# VM_Motor_v0t8.net
KiCad netlist of a schematic drawn in EAGLE
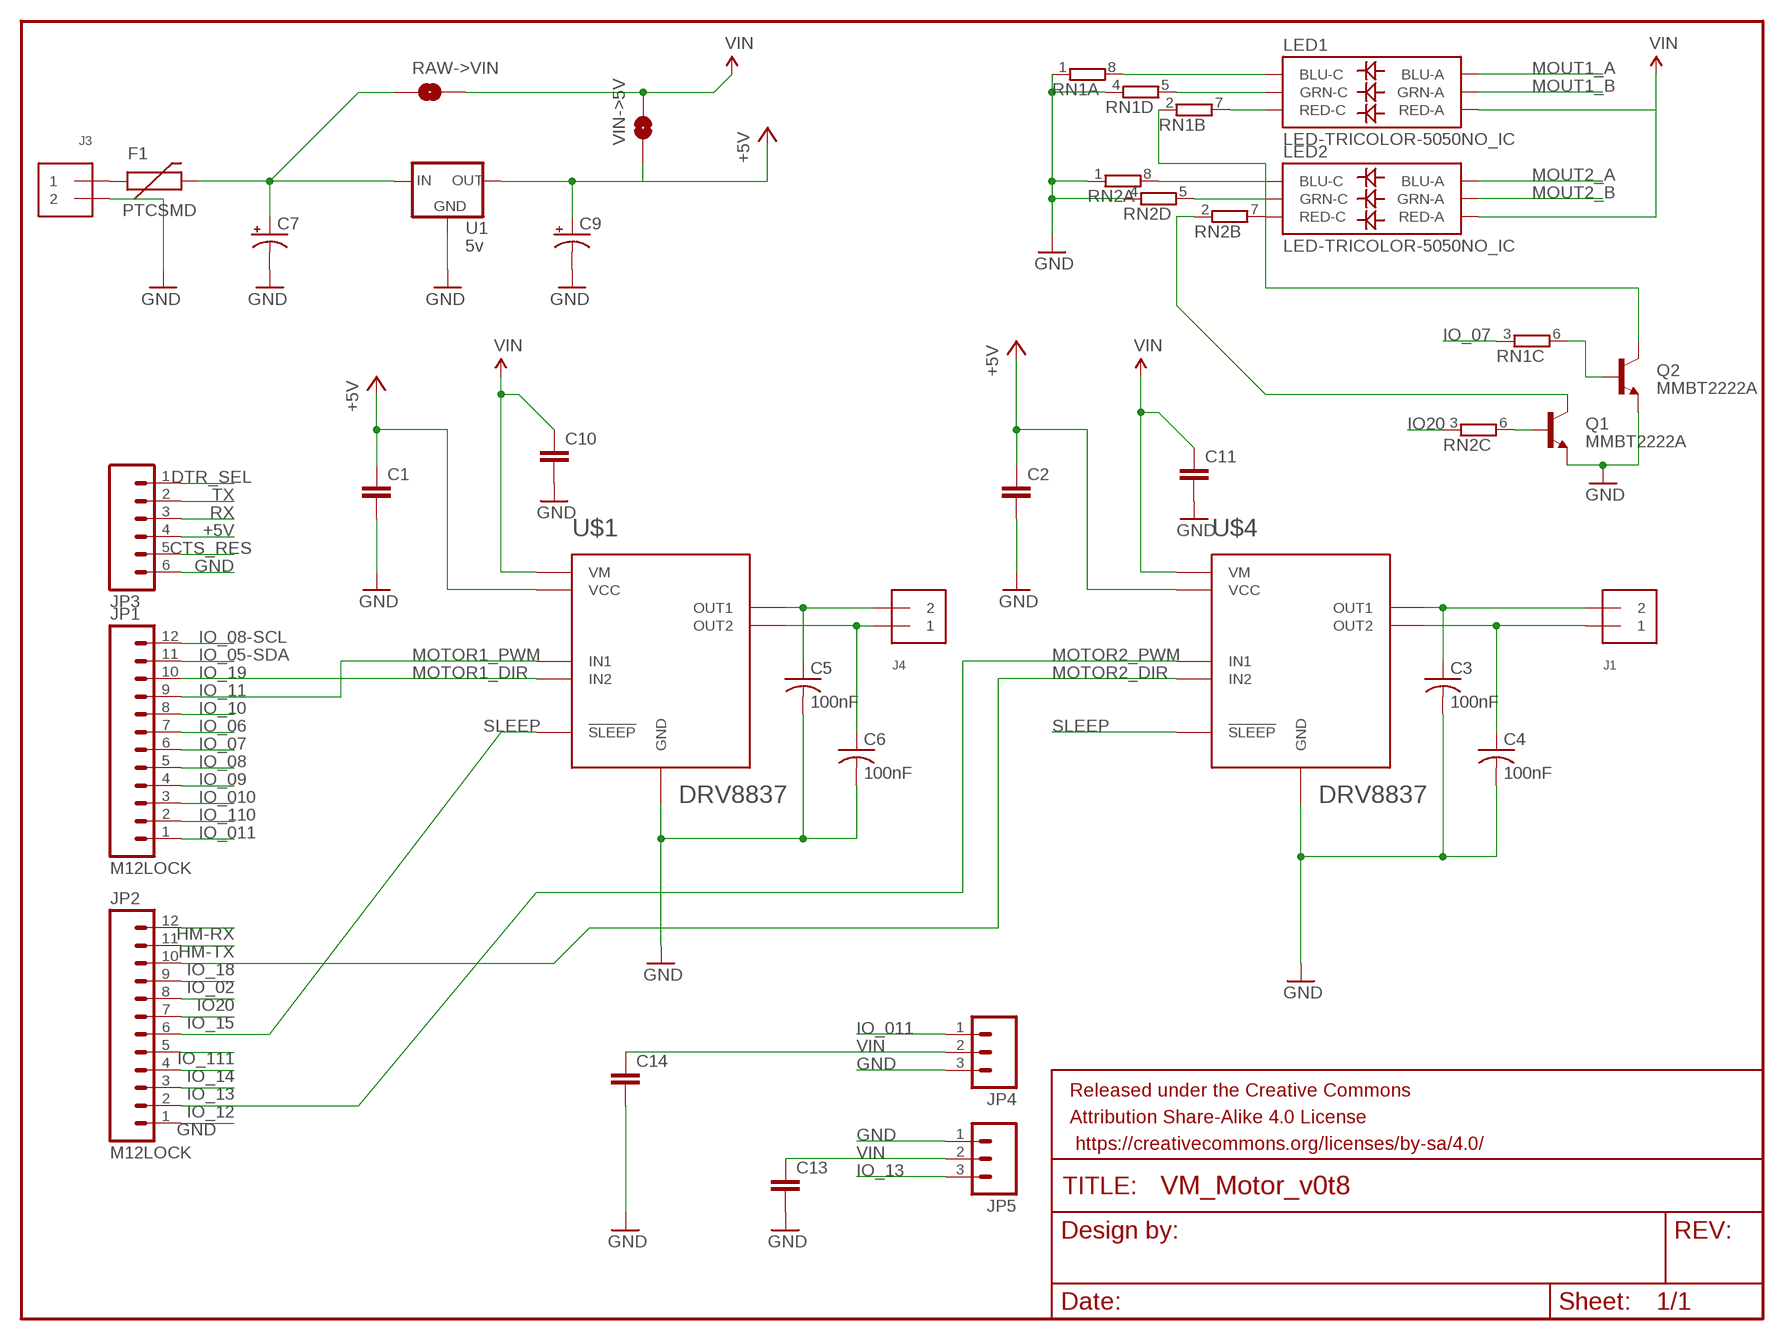
[diagram p0: schematic, sheet 1]

(export (version "E")
  (design (tool "Eeschema 10.0.6"))
  (components
    (comp (ref "C1")
      (value "CAP0402-CAP")
      (footprint "eagle-import:0402-CAP")
      (libsource (lib "eagle-import") (part "CAP0402-CAP"))
    )
    (comp (ref "C2")
      (value "CAP0402-CAP")
      (footprint "eagle-import:0402-CAP")
      (libsource (lib "eagle-import") (part "CAP0402-CAP"))
    )
    (comp (ref "C3")
      (value "100nF")
      (footprint "eagle-import:C0402")
      (libsource (lib "eagle-import") (part "C-USC0402"))
    )
    (comp (ref "C4")
      (value "100nF")
      (footprint "eagle-import:C0402")
      (libsource (lib "eagle-import") (part "C-USC0402"))
    )
    (comp (ref "C5")
      (value "100nF")
      (footprint "eagle-import:C0402")
      (libsource (lib "eagle-import") (part "C-USC0402"))
    )
    (comp (ref "C6")
      (value "100nF")
      (footprint "eagle-import:C0402")
      (libsource (lib "eagle-import") (part "C-USC0402"))
    )
    (comp (ref "C7")
      (value "CPOL-US150CLZ-0810")
      (footprint "eagle-import:150CLZ-0810")
      (libsource (lib "eagle-import") (part "CPOL-US150CLZ-0810"))
    )
    (comp (ref "C9")
      (value "CPOL-US150CLZ-0810")
      (footprint "eagle-import:150CLZ-0810")
      (libsource (lib "eagle-import") (part "CPOL-US150CLZ-0810"))
    )
    (comp (ref "C10")
      (value "CAP0402-CAP")
      (footprint "eagle-import:0402-CAP")
      (libsource (lib "eagle-import") (part "CAP0402-CAP"))
    )
    (comp (ref "C11")
      (value "CAP0402-CAP")
      (footprint "eagle-import:0402-CAP")
      (libsource (lib "eagle-import") (part "CAP0402-CAP"))
    )
    (comp (ref "C13")
      (value "CAP0402-CAP")
      (footprint "eagle-import:0402-CAP")
      (libsource (lib "eagle-import") (part "CAP0402-CAP"))
    )
    (comp (ref "C14")
      (value "CAP0402-CAP")
      (footprint "eagle-import:0402-CAP")
      (libsource (lib "eagle-import") (part "CAP0402-CAP"))
    )
    (comp (ref "F1")
      (value "PTCSMD")
      (footprint "eagle-import:PTC-1206")
      (libsource (lib "eagle-import") (part "PTCSMD"))
    )
    (comp (ref "FRAME1")
      (value "FRAME-LETTER")
      (footprint "eagle-import:CREATIVE_COMMONS")
      (libsource (lib "eagle-import") (part "FRAME-LETTER"))
    )
    (comp (ref "J1")
      (value "TERMBLOCK_1X2")
      (footprint "eagle-import:TERMBLOCK_1X2-3.5MM")
      (libsource (lib "eagle-import") (part "TERMBLOCK_1X2"))
    )
    (comp (ref "J3")
      (value "TERMBLOCK_1X2")
      (footprint "eagle-import:TERMBLOCK_1X2-3.5MM")
      (libsource (lib "eagle-import") (part "TERMBLOCK_1X2"))
    )
    (comp (ref "J4")
      (value "TERMBLOCK_1X2")
      (footprint "eagle-import:TERMBLOCK_1X2-3.5MM")
      (libsource (lib "eagle-import") (part "TERMBLOCK_1X2"))
    )
    (comp (ref "JP1")
      (value "M12LOCK")
      (footprint "eagle-import:1X12_LOCK")
      (libsource (lib "eagle-import") (part "M12LOCK"))
    )
    (comp (ref "JP2")
      (value "M12LOCK")
      (footprint "eagle-import:1X12_LOCK")
      (libsource (lib "eagle-import") (part "M12LOCK"))
    )
    (comp (ref "JP3")
      (value "M06LOCK")
      (footprint "eagle-import:1X06_LOCK")
      (libsource (lib "eagle-import") (part "M06LOCK"))
    )
    (comp (ref "JP4")
      (value "M03LOCK")
      (footprint "eagle-import:1X03_LOCK")
      (libsource (lib "eagle-import") (part "M03LOCK"))
    )
    (comp (ref "JP5")
      (value "M03LOCK")
      (footprint "eagle-import:1X03_LOCK")
      (libsource (lib "eagle-import") (part "M03LOCK"))
    )
    (comp (ref "LED1")
      (value "LED-TRICOLOR-5050NO_IC")
      (footprint "eagle-import:LED-TRICOLOR-5050")
      (libsource (lib "eagle-import") (part "LED-TRICOLOR-5050NO_IC"))
    )
    (comp (ref "LED2")
      (value "LED-TRICOLOR-5050NO_IC")
      (footprint "eagle-import:LED-TRICOLOR-5050")
      (libsource (lib "eagle-import") (part "LED-TRICOLOR-5050NO_IC"))
    )
    (comp (ref "Q1")
      (value "MMBT2222A")
      (footprint "eagle-import:SOT23-3")
      (libsource (lib "eagle-import") (part "TRANSISTOR_NPNMMBT2222A"))
    )
    (comp (ref "Q2")
      (value "MMBT2222A")
      (footprint "eagle-import:SOT23-3")
      (libsource (lib "eagle-import") (part "TRANSISTOR_NPNMMBT2222A"))
    )
    (comp (ref "RAW->VIN")
      (value "SOLDERJUMPERNO")
      (footprint "eagle-import:SJ_2S-NO")
      (libsource (lib "eagle-import") (part "SOLDERJUMPERNO"))
    )
    (comp (ref "RN1")
      (value "4R-N0402ARV341")
      (footprint "eagle-import:4X0402ARV341")
      (libsource (lib "eagle-import") (part "4R-N0402ARV341"))
    )
    (comp (ref "RN2")
      (value "4R-N0402ARV341")
      (footprint "eagle-import:4X0402ARV341")
      (libsource (lib "eagle-import") (part "4R-N0402ARV341"))
    )
    (comp (ref "U$1")
      (value "DRV8837")
      (footprint "eagle-import:QFN8")
      (libsource (lib "eagle-import") (part "DRV8837"))
    )
    (comp (ref "U$4")
      (value "DRV8837")
      (footprint "eagle-import:QFN8")
      (libsource (lib "eagle-import") (part "DRV8837"))
    )
    (comp (ref "U1")
      (value "5v")
      (footprint "eagle-import:DPAK")
      (libsource (lib "eagle-import") (part "V_REG_MC33269DT"))
    )
    (comp (ref "VIN->5V")
      (value "SOLDERJUMPERNO")
      (footprint "eagle-import:SJ_2S-NO")
      (libsource (lib "eagle-import") (part "SOLDERJUMPERNO"))
    )
  )
  (nets
    (net (code "1") (name "+5V") (class "Default")
      (node (ref "C1") (pin "1") (pinfunction "1_1") (pintype "passive"))
      (node (ref "C2") (pin "1") (pinfunction "1_1") (pintype "passive"))
      (node (ref "C9") (pin "+") (pinfunction "+_+") (pintype "passive"))
      (node (ref "JP3") (pin "4") (pinfunction "4_4") (pintype "passive"))
      (node (ref "U$1") (pin "P$8") (pinfunction "VCC_P$8") (pintype "bidirectional"))
      (node (ref "U$4") (pin "P$8") (pinfunction "VCC_P$8") (pintype "bidirectional"))
      (node (ref "U1") (pin "4") (pinfunction "OUT_4") (pintype "output"))
      (node (ref "VIN->5V") (pin "1") (pinfunction "1_1") (pintype "passive"))
    )
    (net (code "2") (name "/CTS_RES") (class "Default")
      (node (ref "JP3") (pin "5") (pinfunction "5_5") (pintype "passive"))
    )
    (net (code "3") (name "/DTR_SEL") (class "Default")
      (node (ref "JP3") (pin "1") (pinfunction "1_1") (pintype "passive"))
    )
    (net (code "4") (name "/HM-RX") (class "Default")
      (node (ref "JP2") (pin "12") (pinfunction "12_12") (pintype "passive"))
    )
    (net (code "5") (name "/HM-TX") (class "Default")
      (node (ref "JP2") (pin "11") (pinfunction "11_11") (pintype "passive"))
    )
    (net (code "6") (name "/IO20") (class "Default")
      (node (ref "JP2") (pin "8") (pinfunction "8_8") (pintype "passive"))
      (node (ref "RN2") (pin "3") (pinfunction "1_3") (pintype "passive"))
    )
    (net (code "7") (name "/IO_02") (class "Default")
      (node (ref "JP2") (pin "9") (pinfunction "9_9") (pintype "passive"))
    )
    (net (code "8") (name "/IO_05-SDA") (class "Default")
      (node (ref "JP1") (pin "11") (pinfunction "11_11") (pintype "passive"))
    )
    (net (code "9") (name "/IO_06") (class "Default")
      (node (ref "JP1") (pin "7") (pinfunction "7_7") (pintype "passive"))
    )
    (net (code "10") (name "/IO_07") (class "Default")
      (node (ref "JP1") (pin "6") (pinfunction "6_6") (pintype "passive"))
      (node (ref "RN1") (pin "3") (pinfunction "1_3") (pintype "passive"))
    )
    (net (code "11") (name "/IO_08") (class "Default")
      (node (ref "JP1") (pin "5") (pinfunction "5_5") (pintype "passive"))
    )
    (net (code "12") (name "/IO_08-SCL") (class "Default")
      (node (ref "JP1") (pin "12") (pinfunction "12_12") (pintype "passive"))
    )
    (net (code "13") (name "/IO_09") (class "Default")
      (node (ref "JP1") (pin "4") (pinfunction "4_4") (pintype "passive"))
    )
    (net (code "14") (name "/IO_10") (class "Default")
      (node (ref "JP1") (pin "8") (pinfunction "8_8") (pintype "passive"))
    )
    (net (code "15") (name "/IO_010") (class "Default")
      (node (ref "JP1") (pin "3") (pinfunction "3_3") (pintype "passive"))
    )
    (net (code "16") (name "/IO_011") (class "Default")
      (node (ref "JP1") (pin "1") (pinfunction "1_1") (pintype "passive"))
      (node (ref "JP4") (pin "1") (pinfunction "1_1") (pintype "passive"))
    )
    (net (code "17") (name "/IO_13") (class "Default")
      (node (ref "JP2") (pin "3") (pinfunction "3_3") (pintype "passive"))
      (node (ref "JP5") (pin "3") (pinfunction "3_3") (pintype "passive"))
    )
    (net (code "18") (name "/IO_14") (class "Default")
      (node (ref "JP2") (pin "4") (pinfunction "4_4") (pintype "passive"))
    )
    (net (code "19") (name "/IO_15") (class "Default")
      (node (ref "JP2") (pin "7") (pinfunction "7_7") (pintype "passive"))
    )
    (net (code "20") (name "/IO_110") (class "Default")
      (node (ref "JP1") (pin "2") (pinfunction "2_2") (pintype "passive"))
    )
    (net (code "21") (name "/IO_111") (class "Default")
      (node (ref "JP2") (pin "5") (pinfunction "5_5") (pintype "passive"))
    )
    (net (code "22") (name "/MOTOR1_DIR") (class "Default")
      (node (ref "JP1") (pin "10") (pinfunction "10_10") (pintype "passive"))
      (node (ref "U$1") (pin "P$5") (pinfunction "IN2_P$5") (pintype "bidirectional"))
    )
    (net (code "23") (name "/MOTOR1_PWM") (class "Default")
      (node (ref "JP1") (pin "9") (pinfunction "9_9") (pintype "passive"))
      (node (ref "U$1") (pin "P$6") (pinfunction "IN1_P$6") (pintype "bidirectional"))
    )
    (net (code "24") (name "/MOTOR2_DIR") (class "Default")
      (node (ref "JP2") (pin "10") (pinfunction "10_10") (pintype "passive"))
      (node (ref "U$4") (pin "P$5") (pinfunction "IN2_P$5") (pintype "bidirectional"))
    )
    (net (code "25") (name "/MOTOR2_PWM") (class "Default")
      (node (ref "JP2") (pin "2") (pinfunction "2_2") (pintype "passive"))
      (node (ref "U$4") (pin "P$6") (pinfunction "IN1_P$6") (pintype "bidirectional"))
    )
    (net (code "26") (name "/MOUT1_A") (class "Default")
      (node (ref "C5") (pin "1") (pinfunction "1_1") (pintype "passive"))
      (node (ref "J4") (pin "2") (pinfunction "2_2") (pintype "passive"))
      (node (ref "LED1") (pin "3") (pinfunction "BLU-A_3") (pintype "bidirectional"))
      (node (ref "U$1") (pin "P$2") (pinfunction "OUT1_P$2") (pintype "bidirectional"))
    )
    (net (code "27") (name "/MOUT1_B") (class "Default")
      (node (ref "C6") (pin "1") (pinfunction "1_1") (pintype "passive"))
      (node (ref "J4") (pin "1") (pinfunction "1_1") (pintype "passive"))
      (node (ref "LED1") (pin "1") (pinfunction "GRN-A_1") (pintype "bidirectional"))
      (node (ref "U$1") (pin "P$3") (pinfunction "OUT2_P$3") (pintype "bidirectional"))
    )
    (net (code "28") (name "/MOUT2_A") (class "Default")
      (node (ref "C3") (pin "1") (pinfunction "1_1") (pintype "passive"))
      (node (ref "J1") (pin "2") (pinfunction "2_2") (pintype "passive"))
      (node (ref "LED2") (pin "3") (pinfunction "BLU-A_3") (pintype "bidirectional"))
      (node (ref "U$4") (pin "P$2") (pinfunction "OUT1_P$2") (pintype "bidirectional"))
    )
    (net (code "29") (name "/MOUT2_B") (class "Default")
      (node (ref "C4") (pin "1") (pinfunction "1_1") (pintype "passive"))
      (node (ref "J1") (pin "1") (pinfunction "1_1") (pintype "passive"))
      (node (ref "LED2") (pin "1") (pinfunction "GRN-A_1") (pintype "bidirectional"))
      (node (ref "U$4") (pin "P$3") (pinfunction "OUT2_P$3") (pintype "bidirectional"))
    )
    (net (code "30") (name "/RX") (class "Default")
      (node (ref "JP3") (pin "3") (pinfunction "3_3") (pintype "passive"))
    )
    (net (code "31") (name "/SLEEP") (class "Default")
      (node (ref "JP2") (pin "6") (pinfunction "6_6") (pintype "passive"))
      (node (ref "U$1") (pin "P$7") (pinfunction "~{SLEEP}_P$7") (pintype "bidirectional"))
      (node (ref "U$4") (pin "P$7") (pinfunction "~{SLEEP}_P$7") (pintype "bidirectional"))
    )
    (net (code "32") (name "/TX") (class "Default")
      (node (ref "JP3") (pin "2") (pinfunction "2_2") (pintype "passive"))
    )
    (net (code "33") (name "GND") (class "Default")
      (node (ref "C1") (pin "2") (pinfunction "2_2") (pintype "passive"))
      (node (ref "C10") (pin "2") (pinfunction "2_2") (pintype "passive"))
      (node (ref "C11") (pin "2") (pinfunction "2_2") (pintype "passive"))
      (node (ref "C13") (pin "2") (pinfunction "2_2") (pintype "passive"))
      (node (ref "C14") (pin "2") (pinfunction "2_2") (pintype "passive"))
      (node (ref "C2") (pin "2") (pinfunction "2_2") (pintype "passive"))
      (node (ref "C3") (pin "2") (pinfunction "2_2") (pintype "passive"))
      (node (ref "C4") (pin "2") (pinfunction "2_2") (pintype "passive"))
      (node (ref "C5") (pin "2") (pinfunction "2_2") (pintype "passive"))
      (node (ref "C6") (pin "2") (pinfunction "2_2") (pintype "passive"))
      (node (ref "C7") (pin "-") (pinfunction "-_-") (pintype "passive"))
      (node (ref "C9") (pin "-") (pinfunction "-_-") (pintype "passive"))
      (node (ref "J3") (pin "2") (pinfunction "2_2") (pintype "passive"))
      (node (ref "JP2") (pin "1") (pinfunction "1_1") (pintype "passive"))
      (node (ref "JP3") (pin "6") (pinfunction "6_6") (pintype "passive"))
      (node (ref "JP4") (pin "3") (pinfunction "3_3") (pintype "passive"))
      (node (ref "JP5") (pin "1") (pinfunction "1_1") (pintype "passive"))
      (node (ref "Q1") (pin "2") (pinfunction "E_2") (pintype "passive"))
      (node (ref "Q2") (pin "2") (pinfunction "E_2") (pintype "passive"))
      (node (ref "RN1") (pin "1") (pinfunction "1_1") (pintype "passive"))
      (node (ref "RN1") (pin "4") (pinfunction "1_4") (pintype "passive"))
      (node (ref "RN2") (pin "1") (pinfunction "1_1") (pintype "passive"))
      (node (ref "RN2") (pin "4") (pinfunction "1_4") (pintype "passive"))
      (node (ref "U$1") (pin "P$10") (pinfunction "GND_P$10") (pintype "bidirectional"))
      (node (ref "U$1") (pin "P$11") (pinfunction "GND_P$11") (pintype "bidirectional"))
      (node (ref "U$1") (pin "P$4") (pinfunction "GND_P$4") (pintype "bidirectional"))
      (node (ref "U$1") (pin "P$9") (pinfunction "GND_P$9") (pintype "bidirectional"))
      (node (ref "U$4") (pin "P$10") (pinfunction "GND_P$10") (pintype "bidirectional"))
      (node (ref "U$4") (pin "P$11") (pinfunction "GND_P$11") (pintype "bidirectional"))
      (node (ref "U$4") (pin "P$4") (pinfunction "GND_P$4") (pintype "bidirectional"))
      (node (ref "U$4") (pin "P$9") (pinfunction "GND_P$9") (pintype "bidirectional"))
      (node (ref "U1") (pin "1") (pinfunction "GND_1") (pintype "input"))
    )
    (net (code "34") (name "Net-(F1-Pad1)") (class "Default")
      (node (ref "F1") (pin "1") (pinfunction "1_1") (pintype "bidirectional"))
      (node (ref "J3") (pin "1") (pinfunction "1_1") (pintype "passive"))
    )
    (net (code "35") (name "Net-(LED1-BLU-C)") (class "Default")
      (node (ref "LED1") (pin "4") (pinfunction "BLU-C_4") (pintype "bidirectional"))
      (node (ref "RN1") (pin "8") (pinfunction "2_8") (pintype "passive"))
    )
    (net (code "36") (name "Net-(LED1-GRN-C)") (class "Default")
      (node (ref "LED1") (pin "6") (pinfunction "GRN-C_6") (pintype "bidirectional"))
      (node (ref "RN1") (pin "5") (pinfunction "2_5") (pintype "passive"))
    )
    (net (code "37") (name "Net-(LED1-RED-C)") (class "Default")
      (node (ref "LED1") (pin "5") (pinfunction "RED-C_5") (pintype "bidirectional"))
      (node (ref "RN1") (pin "7") (pinfunction "2_7") (pintype "passive"))
    )
    (net (code "38") (name "Net-(LED2-BLU-C)") (class "Default")
      (node (ref "LED2") (pin "4") (pinfunction "BLU-C_4") (pintype "bidirectional"))
      (node (ref "RN2") (pin "8") (pinfunction "2_8") (pintype "passive"))
    )
    (net (code "39") (name "Net-(LED2-GRN-C)") (class "Default")
      (node (ref "LED2") (pin "6") (pinfunction "GRN-C_6") (pintype "bidirectional"))
      (node (ref "RN2") (pin "5") (pinfunction "2_5") (pintype "passive"))
    )
    (net (code "40") (name "Net-(LED2-RED-C)") (class "Default")
      (node (ref "LED2") (pin "5") (pinfunction "RED-C_5") (pintype "bidirectional"))
      (node (ref "RN2") (pin "7") (pinfunction "2_7") (pintype "passive"))
    )
    (net (code "41") (name "Net-(Q1-B)") (class "Default")
      (node (ref "Q1") (pin "1") (pinfunction "B_1") (pintype "passive"))
      (node (ref "RN2") (pin "6") (pinfunction "2_6") (pintype "passive"))
    )
    (net (code "42") (name "Net-(Q1-C)") (class "Default")
      (node (ref "Q1") (pin "3") (pinfunction "C_3") (pintype "passive"))
      (node (ref "RN2") (pin "2") (pinfunction "1_2") (pintype "passive"))
    )
    (net (code "43") (name "Net-(Q2-B)") (class "Default")
      (node (ref "Q2") (pin "1") (pinfunction "B_1") (pintype "passive"))
      (node (ref "RN1") (pin "6") (pinfunction "2_6") (pintype "passive"))
    )
    (net (code "44") (name "Net-(Q2-C)") (class "Default")
      (node (ref "Q2") (pin "3") (pinfunction "C_3") (pintype "passive"))
      (node (ref "RN1") (pin "2") (pinfunction "1_2") (pintype "passive"))
    )
    (net (code "45") (name "Net-(U1-IN)") (class "Default")
      (node (ref "C7") (pin "+") (pinfunction "+_+") (pintype "passive"))
      (node (ref "F1") (pin "2") (pinfunction "2_2") (pintype "bidirectional"))
      (node (ref "RAW->VIN") (pin "1") (pinfunction "1_1") (pintype "passive"))
      (node (ref "U1") (pin "3") (pinfunction "IN_3") (pintype "input"))
    )
    (net (code "46") (name "VIN") (class "Default")
      (node (ref "C10") (pin "1") (pinfunction "1_1") (pintype "passive"))
      (node (ref "C11") (pin "1") (pinfunction "1_1") (pintype "passive"))
      (node (ref "C13") (pin "1") (pinfunction "1_1") (pintype "passive"))
      (node (ref "C14") (pin "1") (pinfunction "1_1") (pintype "passive"))
      (node (ref "JP4") (pin "2") (pinfunction "2_2") (pintype "passive"))
      (node (ref "JP5") (pin "2") (pinfunction "2_2") (pintype "passive"))
      (node (ref "LED1") (pin "2") (pinfunction "RED-A_2") (pintype "bidirectional"))
      (node (ref "LED2") (pin "2") (pinfunction "RED-A_2") (pintype "bidirectional"))
      (node (ref "RAW->VIN") (pin "2") (pinfunction "2_2") (pintype "passive"))
      (node (ref "U$1") (pin "P$1") (pinfunction "VM_P$1") (pintype "bidirectional"))
      (node (ref "U$4") (pin "P$1") (pinfunction "VM_P$1") (pintype "bidirectional"))
      (node (ref "VIN->5V") (pin "2") (pinfunction "2_2") (pintype "passive"))
    )
  )
)
